# MCU_SAMD_ATSAMD21G18A-MU.net
KiCad netlist of a schematic drawn in Altium Designer
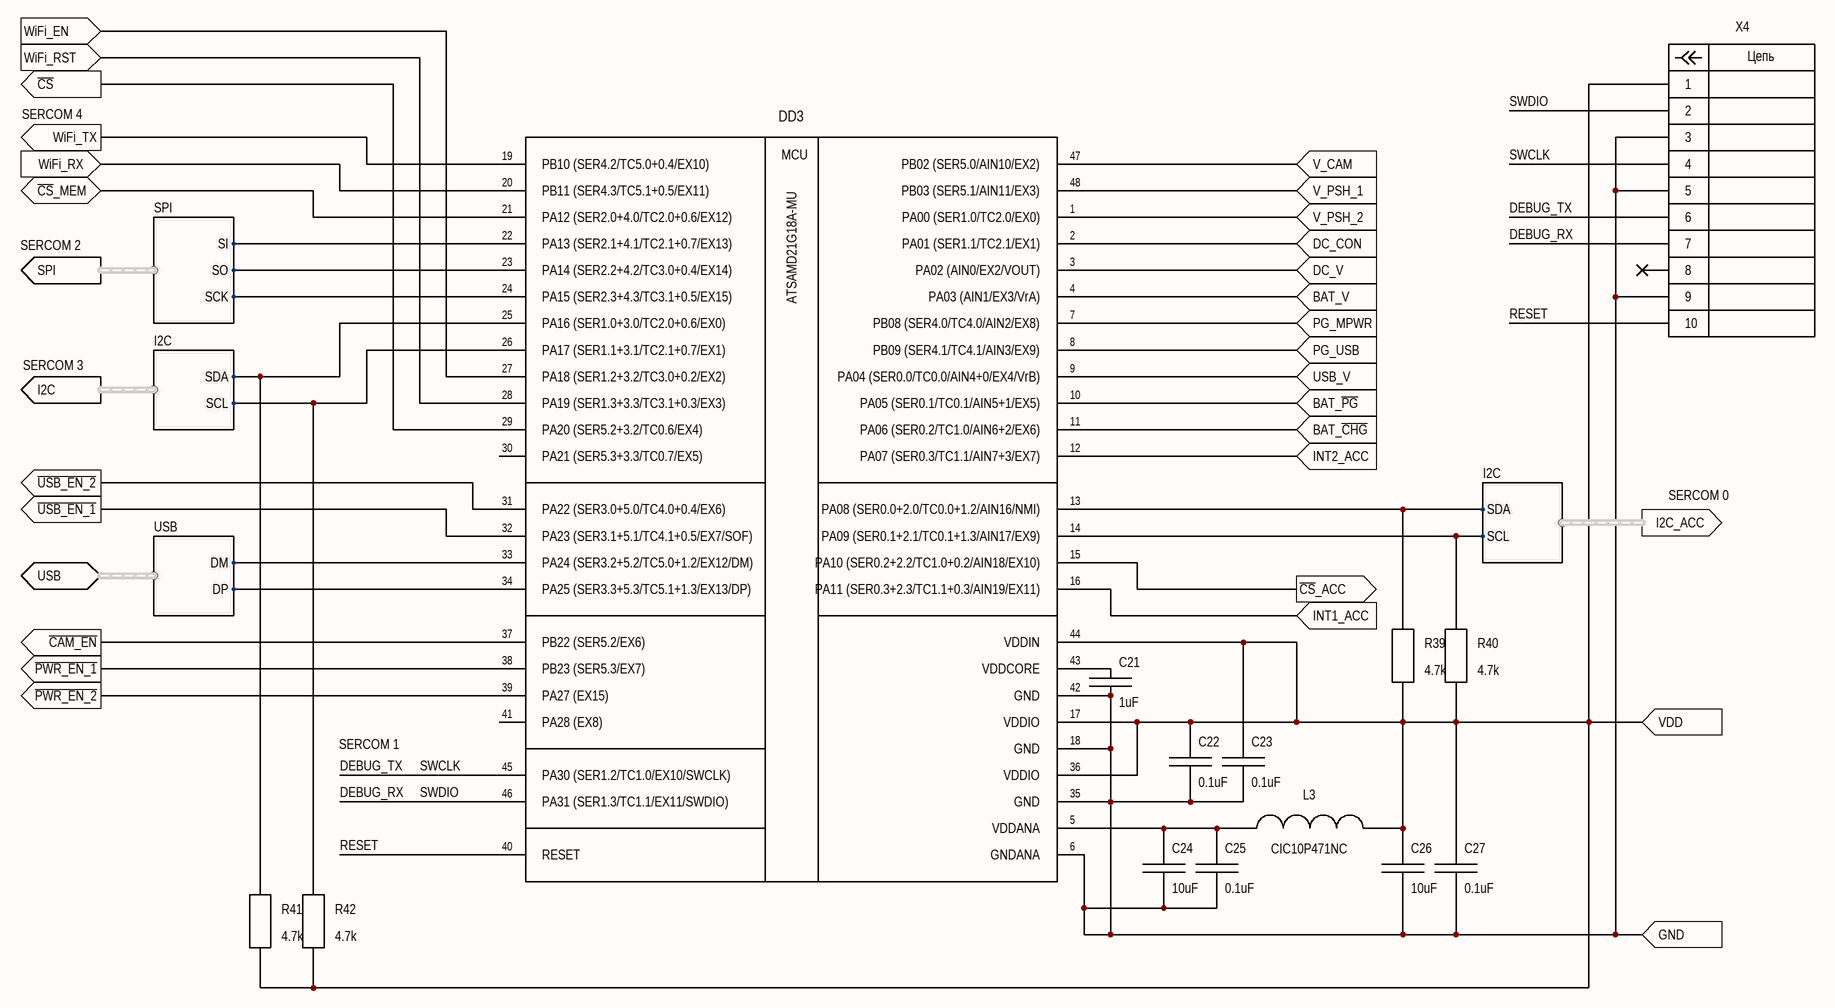
[diagram p0: MCU SAMD ATSAMD21G18A-MU.SchDoc]

(export (version "E")
  (design (tool "Eeschema 10.0.6"))
  (components
    (comp (ref "C21")
      (value "1uF")
      (footprint "CAPC1608L")
      (description "Capacitor Ceramic 1uF 25V")
      (fields (field (name "TOLERANCE") "±10%") (field (name "MANUFACTURER") "Yageo"))
      (libsource (lib "Capacitors") (part "CC0603KRX5R8BB105"))
    )
    (comp (ref "C22")
      (value "0.1uF")
      (footprint "CAPC1608L")
      (description "Capacitor Ceramic 0.1uF 25V")
      (fields (field (name "TOLERANCE") "±10%") (field (name "MANUFACTURER") "Yageo"))
      (libsource (lib "Capacitors") (part "CC0603KRX7R8BB104"))
    )
    (comp (ref "C23")
      (value "0.1uF")
      (footprint "CAPC1608L")
      (description "Capacitor Ceramic 0.1uF 25V")
      (fields (field (name "TOLERANCE") "±10%") (field (name "MANUFACTURER") "Yageo"))
      (libsource (lib "Capacitors") (part "CC0603KRX7R8BB104"))
    )
    (comp (ref "C24")
      (value "10uF")
      (footprint "CAPC2012L")
      (description "Capacitor Ceramic 10uF 25V")
      (fields (field (name "TOLERANCE") "±10%") (field (name "MANUFACTURER") "Yageo"))
      (libsource (lib "Capacitors") (part "CC0805KKX5R8BB106"))
    )
    (comp (ref "C25")
      (value "0.1uF")
      (footprint "CAPC1608L")
      (description "Capacitor Ceramic 0.1uF 25V")
      (fields (field (name "TOLERANCE") "±10%") (field (name "MANUFACTURER") "Yageo"))
      (libsource (lib "Capacitors") (part "CC0603KRX7R8BB104"))
    )
    (comp (ref "C26")
      (value "10uF")
      (footprint "CAPC2012L")
      (description "Capacitor Ceramic 10uF 25V")
      (fields (field (name "TOLERANCE") "±10%") (field (name "MANUFACTURER") "Yageo"))
      (libsource (lib "Capacitors") (part "CC0805KKX5R8BB106"))
    )
    (comp (ref "C27")
      (value "0.1uF")
      (footprint "CAPC1608L")
      (description "Capacitor Ceramic 0.1uF 25V")
      (fields (field (name "TOLERANCE") "±10%") (field (name "MANUFACTURER") "Yageo"))
      (libsource (lib "Capacitors") (part "CC0603KRX7R8BB104"))
    )
    (comp (ref "DD3")
      (value "ATSAMD21G18A-MU")
      (footprint "QFN-48")
      (description "MCU SAMD21 Cortex-M0+")
      (fields (field (name "MANUFACTURER") "Atmel"))
      (libsource (lib "ICs") (part "ATSAMD21G18A-MU"))
    )
    (comp (ref "L3")
      (value "CIC10P471NC")
      (footprint "FB1608L")
      (description "Ferrite Bead 1.2A 470Ohm")
      (fields (field (name "MANUFACTURER") "Samsung Electro-Mechanics America"))
      (libsource (lib "Inductors") (part "CIC10P471NC"))
    )
    (comp (ref "R39")
      (value "4.7k")
      (footprint "RESC1608L")
      (description "Resistor Ceramic 4.7k 1608")
      (fields (field (name "MANUFACTURER") "Yageo") (field (name "TOLERANCE") "±5%"))
      (libsource (lib "Resistors") (part "RC0603JR-074K7L"))
    )
    (comp (ref "R40")
      (value "4.7k")
      (footprint "RESC1608L")
      (description "Resistor Ceramic 4.7k 1608")
      (fields (field (name "MANUFACTURER") "Yageo") (field (name "TOLERANCE") "±5%"))
      (libsource (lib "Resistors") (part "RC0603JR-074K7L"))
    )
    (comp (ref "R41")
      (value "4.7k")
      (footprint "RESC1608L")
      (description "Resistor Ceramic 4.7k 1608")
      (fields (field (name "MANUFACTURER") "Yageo") (field (name "TOLERANCE") "±5%"))
      (libsource (lib "Resistors") (part "RC0603JR-074K7L"))
    )
    (comp (ref "R42")
      (value "4.7k")
      (footprint "RESC1608L")
      (description "Resistor Ceramic 4.7k 1608")
      (fields (field (name "MANUFACTURER") "Yageo") (field (name "TOLERANCE") "±5%"))
      (libsource (lib "Resistors") (part "RC0603JR-074K7L"))
    )
    (comp (ref "X4")
      (value "SWD ICE connector")
      (footprint "SWD ICE Connector")
      (description "Debug SWD ICE Pads")
      (fields (field (name "MANUFACTURER") "Atmel"))
      (libsource (lib "Connectors") (part "SWD ICE connector"))
    )
  )
  (nets
    (net (code "4") (name "/BAT_V") (class "Default")
      (node (ref "DD3") (pin "4") (pinfunction "PA03_(AIN1/EX3/VrA)_4") (pintype "passive"))
    )
    (net (code "5") (name "/BAT_~{CHG}") (class "Default")
      (node (ref "DD3") (pin "11") (pinfunction "PA06_(SER0.2/TC1.0/AIN6+2/EX6)_11") (pintype "passive"))
    )
    (net (code "6") (name "/BAT_~{PG}") (class "Default")
      (node (ref "DD3") (pin "10") (pinfunction "PA05_(SER0.1/TC0.1/AIN5+1/EX5)_10") (pintype "passive"))
    )
    (net (code "7") (name "/DC_CON") (class "Default")
      (node (ref "DD3") (pin "2") (pinfunction "PA01_(SER1.1/TC2.1/EX1)_2") (pintype "passive"))
    )
    (net (code "8") (name "/DC_V") (class "Default")
      (node (ref "DD3") (pin "3") (pinfunction "PA02_(AIN0/EX2/VOUT)_3") (pintype "passive"))
    )
    (net (code "9") (name "/DEBUG_RX") (class "Default")
      (node (ref "DD3") (pin "46") (pinfunction "PA31_(SER1.3/TC1.1/EX11/SWDIO)_46") (pintype "passive"))
      (node (ref "X4") (pin "2") (pinfunction "2_2") (pintype "passive"))
      (node (ref "X4") (pin "7") (pinfunction "7_7") (pintype "passive"))
    )
    (net (code "10") (name "/DEBUG_TX") (class "Default")
      (node (ref "DD3") (pin "45") (pinfunction "PA30_(SER1.2/TC1.0/EX10/SWCLK)_45") (pintype "passive"))
      (node (ref "X4") (pin "4") (pinfunction "4_4") (pintype "passive"))
      (node (ref "X4") (pin "6") (pinfunction "6_6") (pintype "passive"))
    )
    (net (code "11") (name "/DM") (class "Default")
      (node (ref "DD3") (pin "33") (pinfunction "PA24_(SER3.2+5.2/TC5.0+1.2/EX12/DM)_33") (pintype "passive"))
    )
    (net (code "12") (name "/DP") (class "Default")
      (node (ref "DD3") (pin "34") (pinfunction "PA25_(SER3.3+5.3/TC5.1+1.3/EX13/DP)_34") (pintype "passive"))
    )
    (net (code "13") (name "/GND") (class "Default")
      (node (ref "C21") (pin "2") (pinfunction "2_2") (pintype "passive"))
      (node (ref "C22") (pin "2") (pinfunction "2_2") (pintype "passive"))
      (node (ref "C23") (pin "2") (pinfunction "2_2") (pintype "passive"))
      (node (ref "C24") (pin "2") (pinfunction "2_2") (pintype "passive"))
      (node (ref "C25") (pin "2") (pinfunction "2_2") (pintype "passive"))
      (node (ref "C26") (pin "2") (pinfunction "2_2") (pintype "passive"))
      (node (ref "C27") (pin "2") (pinfunction "2_2") (pintype "passive"))
      (node (ref "DD3") (pin "18") (pinfunction "GND_18") (pintype "passive"))
      (node (ref "DD3") (pin "35") (pinfunction "GND_35") (pintype "passive"))
      (node (ref "DD3") (pin "42") (pinfunction "GND_42") (pintype "passive"))
      (node (ref "DD3") (pin "6") (pinfunction "GNDANA_6") (pintype "passive"))
      (node (ref "X4") (pin "3") (pinfunction "3_3") (pintype "passive"))
      (node (ref "X4") (pin "5") (pinfunction "5_5") (pintype "passive"))
      (node (ref "X4") (pin "9") (pinfunction "9_9") (pintype "passive"))
    )
    (net (code "14") (name "/INT1_ACC") (class "Default")
      (node (ref "DD3") (pin "16") (pinfunction "PA11_(SER0.3+2.3/TC1.1+0.3/AIN19/EX11)_16") (pintype "passive"))
    )
    (net (code "15") (name "/INT2_ACC") (class "Default")
      (node (ref "DD3") (pin "12") (pinfunction "PA07_(SER0.3/TC1.1/AIN7+3/EX7)_12") (pintype "passive"))
    )
    (net (code "16") (name "/PG_MPWR") (class "Default")
      (node (ref "DD3") (pin "7") (pinfunction "PB08_(SER4.0/TC4.0/AIN2/EX8)_7") (pintype "passive"))
    )
    (net (code "17") (name "/PG_USB") (class "Default")
      (node (ref "DD3") (pin "8") (pinfunction "PB09_(SER4.1/TC4.1/AIN3/EX9)_8") (pintype "passive"))
    )
    (net (code "18") (name "/RESET") (class "Default")
      (node (ref "DD3") (pin "40") (pinfunction "RESET_40") (pintype "passive"))
      (node (ref "X4") (pin "10") (pinfunction "10_10") (pintype "passive"))
    )
    (net (code "19") (name "/SCK") (class "Default")
      (node (ref "DD3") (pin "24") (pinfunction "PA15_(SER2.3+4.3/TC3.1+0.5/EX15)_24") (pintype "passive"))
    )
    (net (code "20") (name "/SI") (class "Default")
      (node (ref "DD3") (pin "22") (pinfunction "PA13_(SER2.1+4.1/TC2.1+0.7/EX13)_22") (pintype "passive"))
    )
    (net (code "21") (name "/SO") (class "Default")
      (node (ref "DD3") (pin "23") (pinfunction "PA14_(SER2.2+4.2/TC3.0+0.4/EX14)_23") (pintype "passive"))
    )
    (net (code "22") (name "/USB_V") (class "Default")
      (node (ref "DD3") (pin "9") (pinfunction "PA04_(SER0.0/TC0.0/AIN4+0/EX4/VrB)_9") (pintype "passive"))
    )
    (net (code "23") (name "/VDD") (class "Default")
      (node (ref "C22") (pin "1") (pinfunction "1_1") (pintype "passive"))
      (node (ref "C23") (pin "1") (pinfunction "1_1") (pintype "passive"))
      (node (ref "C26") (pin "1") (pinfunction "1_1") (pintype "passive"))
      (node (ref "C27") (pin "1") (pinfunction "1_1") (pintype "passive"))
      (node (ref "DD3") (pin "17") (pinfunction "VDDIO_17") (pintype "passive"))
      (node (ref "DD3") (pin "36") (pinfunction "VDDIO_36") (pintype "passive"))
      (node (ref "DD3") (pin "44") (pinfunction "VDDIN_44") (pintype "passive"))
      (node (ref "L3") (pin "2") (pinfunction "2_2") (pintype "passive"))
      (node (ref "R39") (pin "2") (pinfunction "2_2") (pintype "passive"))
      (node (ref "R40") (pin "2") (pinfunction "2_2") (pintype "passive"))
      (node (ref "R41") (pin "2") (pinfunction "2_2") (pintype "passive"))
      (node (ref "R42") (pin "2") (pinfunction "2_2") (pintype "passive"))
      (node (ref "X4") (pin "1") (pinfunction "1_1") (pintype "passive"))
    )
    (net (code "24") (name "/V_CAM") (class "Default")
      (node (ref "DD3") (pin "47") (pinfunction "PB02_(SER5.0/AIN10/EX2)_47") (pintype "passive"))
    )
    (net (code "25") (name "/V_PSH_1") (class "Default")
      (node (ref "DD3") (pin "48") (pinfunction "PB03_(SER5.1/AIN11/EX3)_48") (pintype "passive"))
    )
    (net (code "26") (name "/V_PSH_2") (class "Default")
      (node (ref "DD3") (pin "1") (pinfunction "PA00_(SER1.0/TC2.0/EX0)_1") (pintype "passive"))
    )
    (net (code "27") (name "/WiFi_EN") (class "Default")
      (node (ref "DD3") (pin "27") (pinfunction "PA18_(SER1.2+3.2/TC3.0+0.2/EX2)_27") (pintype "passive"))
    )
    (net (code "28") (name "/WiFi_RST") (class "Default")
      (node (ref "DD3") (pin "28") (pinfunction "PA19_(SER1.3+3.3/TC3.1+0.3/EX3)_28") (pintype "passive"))
    )
    (net (code "29") (name "/WiFi_RX") (class "Default")
      (node (ref "DD3") (pin "20") (pinfunction "PB11_(SER4.3/TC5.1+0.5/EX11)_20") (pintype "passive"))
    )
    (net (code "30") (name "/WiFi_TX") (class "Default")
      (node (ref "DD3") (pin "19") (pinfunction "PB10_(SER4.2/TC5.0+0.4/EX10)_19") (pintype "passive"))
    )
    (net (code "34") (name "/~{CAM_EN}") (class "Default")
      (node (ref "DD3") (pin "37") (pinfunction "PB22_(SER5.2/EX6)_37") (pintype "passive"))
    )
    (net (code "35") (name "/~{CS}") (class "Default")
      (node (ref "DD3") (pin "29") (pinfunction "PA20_(SER5.2+3.2/TC0.6/EX4)_29") (pintype "passive"))
    )
    (net (code "36") (name "/~{CS}_ACC") (class "Default")
      (node (ref "DD3") (pin "15") (pinfunction "PA10_(SER0.2+2.2/TC1.0+0.2/AIN18/EX10)_15") (pintype "passive"))
    )
    (net (code "37") (name "/~{CS}_MEM") (class "Default")
      (node (ref "DD3") (pin "21") (pinfunction "PA12_(SER2.0+4.0/TC2.0+0.6/EX12)_21") (pintype "passive"))
    )
    (net (code "38") (name "/~{PWR_EN_1}") (class "Default")
      (node (ref "DD3") (pin "38") (pinfunction "PB23_(SER5.3/EX7)_38") (pintype "passive"))
    )
    (net (code "39") (name "/~{PWR_EN_2}") (class "Default")
      (node (ref "DD3") (pin "39") (pinfunction "PA27_(EX15)_39") (pintype "passive"))
    )
    (net (code "40") (name "/~{USB_EN_1}") (class "Default")
      (node (ref "DD3") (pin "32") (pinfunction "PA23_(SER3.1+5.1/TC4.1+0.5/EX7/SOF)_32") (pintype "passive"))
    )
    (net (code "41") (name "/~{USB_EN_2}") (class "Default")
      (node (ref "DD3") (pin "31") (pinfunction "PA22_(SER3.0+5.0/TC4.0+0.4/EX6)_31") (pintype "passive"))
    )
    (net (code "42") (name "Net-(DD3-PA08_(SER0.0+2.0{slash}TC0.0+1.2{slash}AIN16{slash}NMI))") (class "Default")
      (node (ref "DD3") (pin "13") (pinfunction "PA08_(SER0.0+2.0/TC0.0+1.2/AIN16/NMI)_13") (pintype "passive"))
      (node (ref "R39") (pin "1") (pinfunction "1_1") (pintype "passive"))
    )
    (net (code "43") (name "Net-(DD3-PA09_(SER0.1+2.1{slash}TC0.1+1.3{slash}AIN17{slash}EX9))") (class "Default")
      (node (ref "DD3") (pin "14") (pinfunction "PA09_(SER0.1+2.1/TC0.1+1.3/AIN17/EX9)_14") (pintype "passive"))
      (node (ref "R40") (pin "1") (pinfunction "1_1") (pintype "passive"))
    )
    (net (code "44") (name "Net-(DD3-PA16_(SER1.0+3.0{slash}TC2.0+0.6{slash}EX0))") (class "Default")
      (node (ref "DD3") (pin "25") (pinfunction "PA16_(SER1.0+3.0/TC2.0+0.6/EX0)_25") (pintype "passive"))
      (node (ref "R41") (pin "1") (pinfunction "1_1") (pintype "passive"))
    )
    (net (code "45") (name "Net-(DD3-PA17_(SER1.1+3.1{slash}TC2.1+0.7{slash}EX1))") (class "Default")
      (node (ref "DD3") (pin "26") (pinfunction "PA17_(SER1.1+3.1/TC2.1+0.7/EX1)_26") (pintype "passive"))
      (node (ref "R42") (pin "1") (pinfunction "1_1") (pintype "passive"))
    )
    (net (code "46") (name "Net-(DD3-VDDANA)") (class "Default")
      (node (ref "C24") (pin "1") (pinfunction "1_1") (pintype "passive"))
      (node (ref "C25") (pin "1") (pinfunction "1_1") (pintype "passive"))
      (node (ref "DD3") (pin "5") (pinfunction "VDDANA_5") (pintype "passive"))
      (node (ref "L3") (pin "1") (pinfunction "1_1") (pintype "passive"))
    )
    (net (code "47") (name "Net-(DD3-VDDCORE)") (class "Default")
      (node (ref "C21") (pin "1") (pinfunction "1_1") (pintype "passive"))
      (node (ref "DD3") (pin "43") (pinfunction "VDDCORE_43") (pintype "passive"))
    )
    (net (code "48") (name "unconnected-(DD3-PA21_(SER5.3+3.3{slash}TC0.7{slash}EX5)-Pad30)") (class "Default")
      (node (ref "DD3") (pin "30") (pinfunction "PA21_(SER5.3+3.3/TC0.7/EX5)_30") (pintype "passive"))
    )
    (net (code "49") (name "unconnected-(DD3-PA28_(EX8)-Pad41)") (class "Default")
      (node (ref "DD3") (pin "41") (pinfunction "PA28_(EX8)_41") (pintype "passive"))
    )
    (net (code "50") (name "unconnected-(X4-Pad8)") (class "Default")
      (node (ref "X4") (pin "8") (pinfunction "8_8") (pintype "passive+no_connect"))
    )
  )
)
